# ESP_SCH_debug_and_testing.net
KiCad netlist of a schematic drawn in Altium Designer
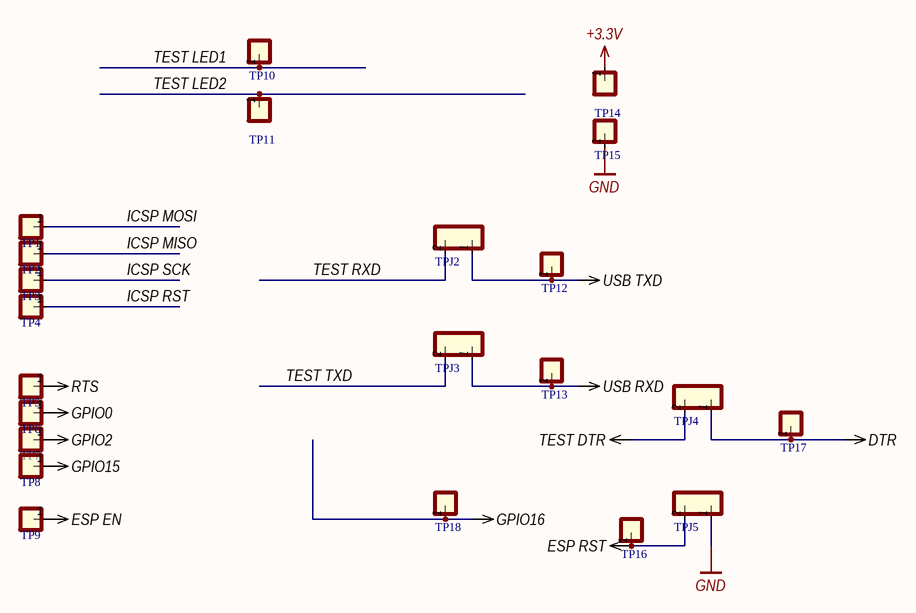
[diagram p0: ESP_SCH_debug and testing.SchDoc]

(export (version "E")
  (design (tool "Eeschema 10.0.6"))
  (components
    (comp (ref "TP1") (value "TP") (footprint "TP no hole") (libsource (lib "Symbols GOST") (part "TP")))
    (comp (ref "TP2") (value "TP") (footprint "TP no hole") (libsource (lib "Symbols GOST") (part "TP")))
    (comp (ref "TP3") (value "TP") (footprint "TP no hole") (libsource (lib "Symbols GOST") (part "TP")))
    (comp (ref "TP4") (value "TP") (footprint "TP no hole") (libsource (lib "Symbols GOST") (part "TP")))
    (comp (ref "TP5") (value "TP") (footprint "TP no hole") (libsource (lib "Symbols GOST") (part "TP")))
    (comp (ref "TP6") (value "TP") (footprint "TP no hole") (libsource (lib "Symbols GOST") (part "TP")))
    (comp (ref "TP7") (value "TP") (footprint "TP no hole") (libsource (lib "Symbols GOST") (part "TP")))
    (comp (ref "TP8") (value "TP") (footprint "TP no hole") (libsource (lib "Symbols GOST") (part "TP")))
    (comp (ref "TP9") (value "TP") (footprint "TP no hole") (libsource (lib "Symbols GOST") (part "TP")))
    (comp (ref "TP10") (value "TP") (footprint "TP no hole") (libsource (lib "") (part "TP_1")))
    (comp (ref "TP11") (value "TP") (footprint "TP no hole") (libsource (lib "") (part "TP_2")))
    (comp (ref "TP12") (value "TP") (footprint "TP no hole") (libsource (lib "") (part "TP_1")))
    (comp (ref "TP13") (value "TP") (footprint "TP no hole") (libsource (lib "") (part "TP_1")))
    (comp (ref "TP14") (value "TP") (footprint "TP no hole") (libsource (lib "") (part "TP_2")))
    (comp (ref "TP15") (value "TP") (footprint "TP no hole") (libsource (lib "") (part "TP_1")))
    (comp (ref "TP16") (value "TP") (footprint "TP no hole") (libsource (lib "") (part "TP_1")))
    (comp (ref "TP17") (value "TP") (footprint "TP no hole") (libsource (lib "") (part "TP_1")))
    (comp (ref "TP18") (value "TP") (footprint "TP no hole") (libsource (lib "") (part "TP_1")))
    (comp (ref "TPJ2")
      (value "Jumper2")
      (footprint "SJ_2S-NO")
      (libsource (lib "Symbols GOST") (part "Jumper2"))
    )
    (comp (ref "TPJ3")
      (value "Jumper2")
      (footprint "SJ_2S-NO")
      (libsource (lib "Symbols GOST") (part "Jumper2"))
    )
    (comp (ref "TPJ4")
      (value "Jumper2")
      (footprint "SJ_2S-NO")
      (libsource (lib "Symbols GOST") (part "Jumper2"))
    )
    (comp (ref "TPJ5")
      (value "Jumper2")
      (footprint "SJ_2S-NO")
      (libsource (lib "Symbols GOST") (part "Jumper2"))
    )
  )
  (nets
    (net (code "1") (name "+3.3V") (class "Default")
      (node (ref "TP14") (pin "1") (pinfunction "PD3_1") (pintype "passive"))
    )
    (net (code "2") (name "/ICSP MISO") (class "Default")
      (node (ref "TP2") (pin "1") (pinfunction "PD3_1") (pintype "passive"))
    )
    (net (code "3") (name "/ICSP MOSI") (class "Default")
      (node (ref "TP1") (pin "1") (pinfunction "PD3_1") (pintype "passive"))
    )
    (net (code "4") (name "/ICSP RST") (class "Default")
      (node (ref "TP4") (pin "1") (pinfunction "PD3_1") (pintype "passive"))
    )
    (net (code "5") (name "/ICSP SCK") (class "Default")
      (node (ref "TP3") (pin "1") (pinfunction "PD3_1") (pintype "passive"))
    )
    (net (code "6") (name "/TEST LED1") (class "Default")
      (node (ref "TP10") (pin "1") (pinfunction "PD3_1") (pintype "passive"))
    )
    (net (code "7") (name "/TEST LED2") (class "Default")
      (node (ref "TP11") (pin "1") (pinfunction "PD3_1") (pintype "passive"))
    )
    (net (code "8") (name "/TEST RXD") (class "Default")
      (node (ref "TPJ2") (pin "2") (pinfunction "PD4_2") (pintype "passive"))
    )
    (net (code "9") (name "/TEST TXD") (class "Default")
      (node (ref "TPJ3") (pin "2") (pinfunction "PD4_2") (pintype "passive"))
    )
    (net (code "10") (name "DTR") (class "Default")
      (node (ref "TP17") (pin "1") (pinfunction "PD3_1") (pintype "passive"))
      (node (ref "TPJ4") (pin "1") (pinfunction "PD3_1") (pintype "passive"))
    )
    (net (code "11") (name "ESP EN") (class "Default")
      (node (ref "TP9") (pin "1") (pinfunction "PD3_1") (pintype "passive"))
    )
    (net (code "12") (name "ESP RST") (class "Default")
      (node (ref "TP16") (pin "1") (pinfunction "PD3_1") (pintype "passive"))
      (node (ref "TPJ5") (pin "2") (pinfunction "PD4_2") (pintype "passive"))
    )
    (net (code "13") (name "GND") (class "Default")
      (node (ref "TP15") (pin "1") (pinfunction "PD3_1") (pintype "passive"))
      (node (ref "TPJ5") (pin "1") (pinfunction "PD3_1") (pintype "passive"))
    )
    (net (code "14") (name "GPIO0") (class "Default")
      (node (ref "TP6") (pin "1") (pinfunction "PD3_1") (pintype "passive"))
    )
    (net (code "15") (name "GPIO2") (class "Default")
      (node (ref "TP7") (pin "1") (pinfunction "PD3_1") (pintype "passive"))
    )
    (net (code "16") (name "GPIO15") (class "Default")
      (node (ref "TP8") (pin "1") (pinfunction "PD3_1") (pintype "passive"))
    )
    (net (code "17") (name "GPIO16") (class "Default")
      (node (ref "TP18") (pin "1") (pinfunction "PD3_1") (pintype "passive"))
    )
    (net (code "18") (name "RTS") (class "Default")
      (node (ref "TP5") (pin "1") (pinfunction "PD3_1") (pintype "passive"))
    )
    (net (code "19") (name "TEST DTR") (class "Default")
      (node (ref "TPJ4") (pin "2") (pinfunction "PD4_2") (pintype "passive"))
    )
    (net (code "20") (name "USB RXD") (class "Default")
      (node (ref "TP13") (pin "1") (pinfunction "PD3_1") (pintype "passive"))
      (node (ref "TPJ3") (pin "1") (pinfunction "PD3_1") (pintype "passive"))
    )
    (net (code "21") (name "USB TXD") (class "Default")
      (node (ref "TP12") (pin "1") (pinfunction "PD3_1") (pintype "passive"))
      (node (ref "TPJ2") (pin "1") (pinfunction "PD3_1") (pintype "passive"))
    )
  )
)
